# PIC18_Peripheral_breakout.net
KiCad netlist of a schematic drawn in EAGLE
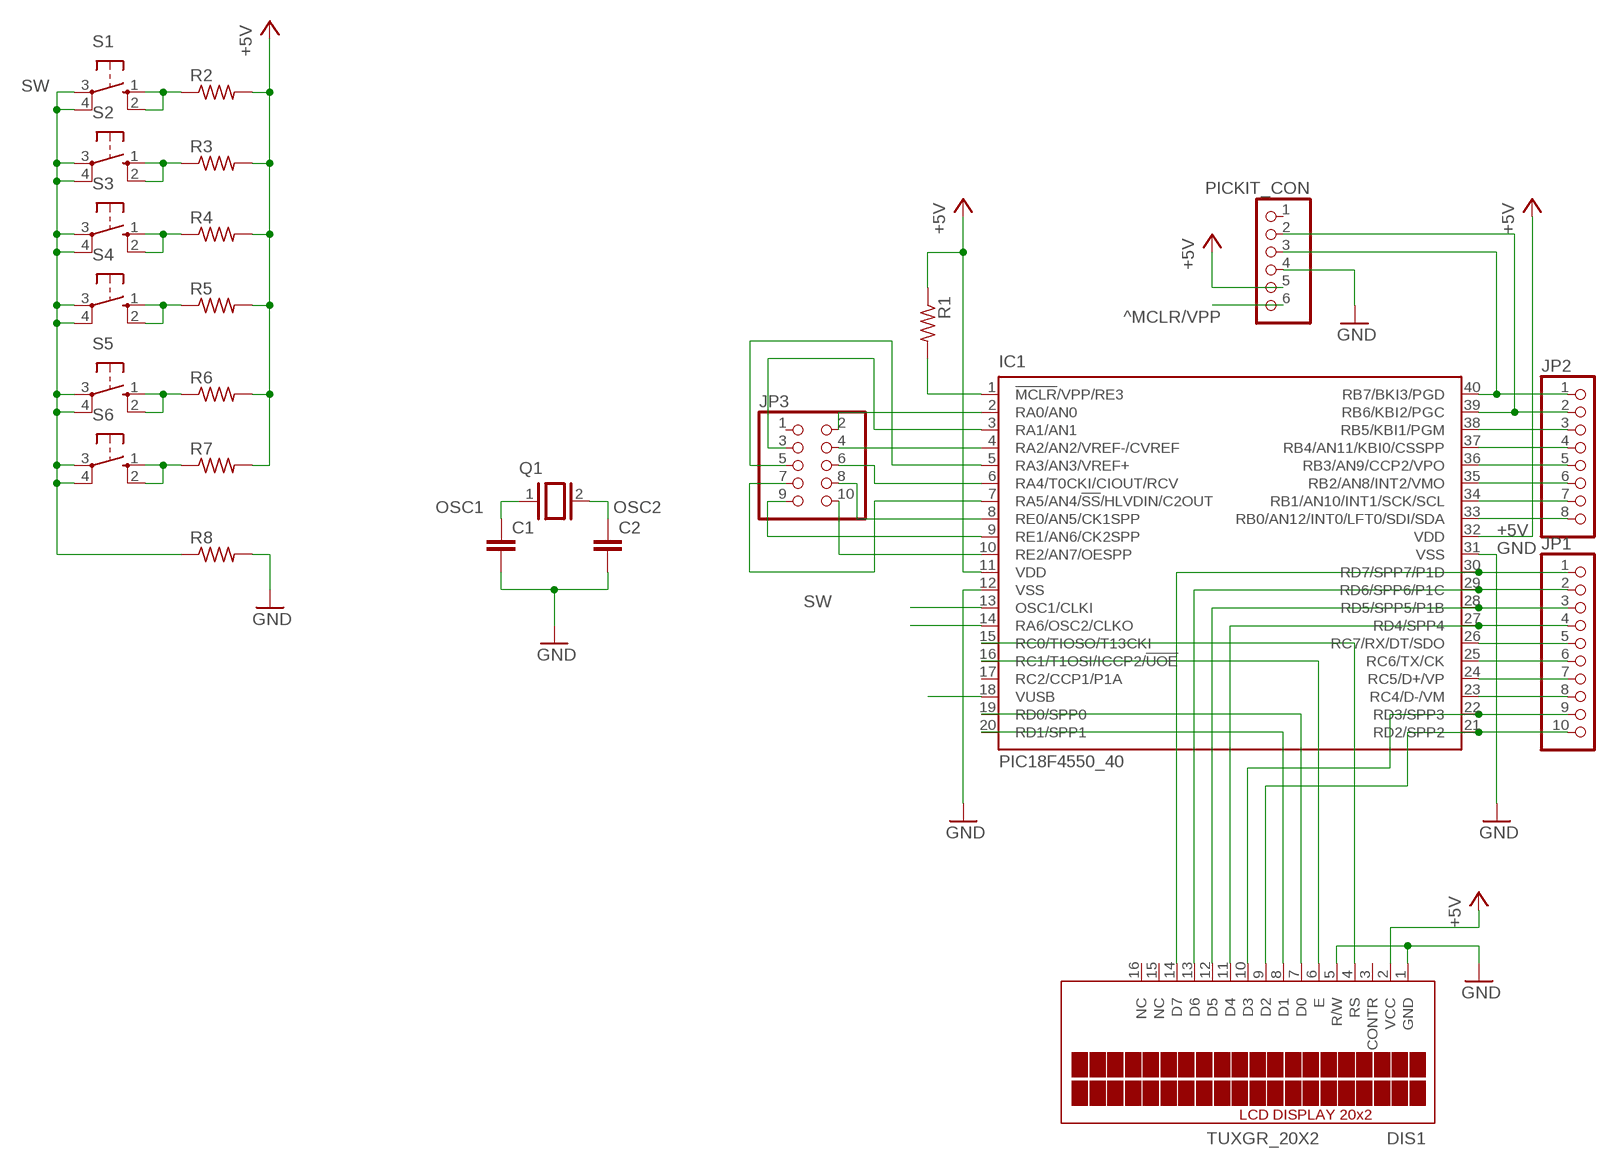
[diagram p0: schematic, sheet 1]

(export (version "E")
  (design (tool "Eeschema 10.0.6"))
  (components
    (comp (ref "C1")
      (value "C-EUC1206")
      (footprint "eagle-import:C1206")
      (libsource (lib "eagle-import") (part "C-EUC1206"))
    )
    (comp (ref "C2")
      (value "C-EUC1206")
      (footprint "eagle-import:C1206")
      (libsource (lib "eagle-import") (part "C-EUC1206"))
    )
    (comp (ref "DIS1")
      (value "TUXGR_20X2")
      (footprint "eagle-import:TUXGR_20X2")
      (libsource (lib "eagle-import") (part "TUXGR_20X2"))
    )
    (comp (ref "IC1")
      (value "PIC18F4550_40")
      (footprint "eagle-import:DIL40")
      (fields (field (name "MF") "MICROCHIP") (field (name "MPN") "PIC18F4550-I/P"))
      (libsource (lib "eagle-import") (part "PIC18F4_40550"))
    )
    (comp (ref "JP1")
      (value "PINHD-1X10")
      (footprint "eagle-import:1X10")
      (libsource (lib "eagle-import") (part "PINHD-1X10"))
    )
    (comp (ref "JP2")
      (value "PINHD-1X8")
      (footprint "eagle-import:1X08")
      (libsource (lib "eagle-import") (part "PINHD-1X8"))
    )
    (comp (ref "JP3")
      (value "PINHD-2X5")
      (footprint "eagle-import:2X05")
      (libsource (lib "eagle-import") (part "PINHD-2X5"))
    )
    (comp (ref "PICKIT_CON")
      (value "PINHD-1X6/90")
      (footprint "eagle-import:1X06_90")
      (libsource (lib "eagle-import") (part "PINHD-1X6/90"))
    )
    (comp (ref "Q1")
      (value "XTAL/S")
      (footprint "eagle-import:QS")
      (libsource (lib "eagle-import") (part "XTAL/S"))
    )
    (comp (ref "R1")
      (value "R-US_R1206")
      (footprint "eagle-import:R1206")
      (libsource (lib "eagle-import") (part "R-US_R1206"))
    )
    (comp (ref "R2")
      (value "R-US_R1206")
      (footprint "eagle-import:R1206")
      (libsource (lib "eagle-import") (part "R-US_R1206"))
    )
    (comp (ref "R3")
      (value "R-US_R1206")
      (footprint "eagle-import:R1206")
      (libsource (lib "eagle-import") (part "R-US_R1206"))
    )
    (comp (ref "R4")
      (value "R-US_R1206")
      (footprint "eagle-import:R1206")
      (libsource (lib "eagle-import") (part "R-US_R1206"))
    )
    (comp (ref "R5")
      (value "R-US_R1206")
      (footprint "eagle-import:R1206")
      (libsource (lib "eagle-import") (part "R-US_R1206"))
    )
    (comp (ref "R6")
      (value "R-US_R1206")
      (footprint "eagle-import:R1206")
      (libsource (lib "eagle-import") (part "R-US_R1206"))
    )
    (comp (ref "R7")
      (value "R-US_R1206")
      (footprint "eagle-import:R1206")
      (libsource (lib "eagle-import") (part "R-US_R1206"))
    )
    (comp (ref "R8")
      (value "R-US_R1206")
      (footprint "eagle-import:R1206")
      (libsource (lib "eagle-import") (part "R-US_R1206"))
    )
    (comp (ref "S1")
      (value "10-XX")
      (footprint "eagle-import:B3F-10XX")
      (fields (field (name "MPN") "B3F-1000"))
      (libsource (lib "eagle-import") (part "10-XX"))
    )
    (comp (ref "S2")
      (value "10-XX")
      (footprint "eagle-import:B3F-10XX")
      (fields (field (name "MPN") "B3F-1000"))
      (libsource (lib "eagle-import") (part "10-XX"))
    )
    (comp (ref "S3")
      (value "10-XX")
      (footprint "eagle-import:B3F-10XX")
      (fields (field (name "MPN") "B3F-1000"))
      (libsource (lib "eagle-import") (part "10-XX"))
    )
    (comp (ref "S4")
      (value "10-XX")
      (footprint "eagle-import:B3F-10XX")
      (fields (field (name "MPN") "B3F-1000"))
      (libsource (lib "eagle-import") (part "10-XX"))
    )
    (comp (ref "S5")
      (value "10-XX")
      (footprint "eagle-import:B3F-10XX")
      (fields (field (name "MPN") "B3F-1000"))
      (libsource (lib "eagle-import") (part "10-XX"))
    )
    (comp (ref "S6")
      (value "10-XX")
      (footprint "eagle-import:B3F-10XX")
      (fields (field (name "MPN") "B3F-1000"))
      (libsource (lib "eagle-import") (part "10-XX"))
    )
  )
  (nets
    (net (code "1") (name "+5V") (class "Default")
      (node (ref "DIS1") (pin "2") (pinfunction "VCC_2") (pintype "power_in"))
      (node (ref "IC1") (pin "11") (pinfunction "VDD_11") (pintype "power_in"))
      (node (ref "IC1") (pin "32") (pinfunction "VDD_32") (pintype "power_in"))
      (node (ref "PICKIT_CON") (pin "5") (pinfunction "5_5") (pintype "passive"))
      (node (ref "R1") (pin "1") (pinfunction "1_1") (pintype "passive"))
      (node (ref "R2") (pin "2") (pinfunction "2_2") (pintype "passive"))
      (node (ref "R3") (pin "2") (pinfunction "2_2") (pintype "passive"))
      (node (ref "R4") (pin "2") (pinfunction "2_2") (pintype "passive"))
      (node (ref "R5") (pin "2") (pinfunction "2_2") (pintype "passive"))
      (node (ref "R6") (pin "2") (pinfunction "2_2") (pintype "passive"))
      (node (ref "R7") (pin "2") (pinfunction "2_2") (pintype "passive"))
    )
    (net (code "2") (name "/OSC1") (class "Default")
      (node (ref "C1") (pin "1") (pinfunction "1_1") (pintype "passive"))
      (node (ref "IC1") (pin "13") (pinfunction "OSC1/CLKI_13") (pintype "input"))
      (node (ref "Q1") (pin "1") (pinfunction "1_1") (pintype "passive"))
    )
    (net (code "3") (name "/OSC2") (class "Default")
      (node (ref "C2") (pin "1") (pinfunction "1_1") (pintype "passive"))
      (node (ref "IC1") (pin "14") (pinfunction "RA6/OSC2/CLKO_14") (pintype "output"))
      (node (ref "Q1") (pin "2") (pinfunction "2_2") (pintype "passive"))
    )
    (net (code "4") (name "/SW") (class "Default")
      (node (ref "IC1") (pin "10") (pinfunction "RE2/AN7/OESPP_10") (pintype "bidirectional"))
      (node (ref "JP3") (pin "10") (pinfunction "10_10") (pintype "passive"))
      (node (ref "R8") (pin "1") (pinfunction "1_1") (pintype "passive"))
      (node (ref "S1") (pin "3") (pinfunction "P_3") (pintype "passive"))
      (node (ref "S1") (pin "4") (pinfunction "P1_4") (pintype "passive"))
      (node (ref "S2") (pin "3") (pinfunction "P_3") (pintype "passive"))
      (node (ref "S2") (pin "4") (pinfunction "P1_4") (pintype "passive"))
      (node (ref "S3") (pin "3") (pinfunction "P_3") (pintype "passive"))
      (node (ref "S3") (pin "4") (pinfunction "P1_4") (pintype "passive"))
      (node (ref "S4") (pin "3") (pinfunction "P_3") (pintype "passive"))
      (node (ref "S4") (pin "4") (pinfunction "P1_4") (pintype "passive"))
      (node (ref "S5") (pin "3") (pinfunction "P_3") (pintype "passive"))
      (node (ref "S5") (pin "4") (pinfunction "P1_4") (pintype "passive"))
      (node (ref "S6") (pin "3") (pinfunction "P_3") (pintype "passive"))
      (node (ref "S6") (pin "4") (pinfunction "P1_4") (pintype "passive"))
    )
    (net (code "5") (name "/^MCLR{slash}VPP") (class "Default")
      (node (ref "IC1") (pin "1") (pinfunction "~{MCLR}/VPP/RE3_1") (pintype "input"))
      (node (ref "PICKIT_CON") (pin "6") (pinfunction "6_6") (pintype "passive"))
      (node (ref "R1") (pin "2") (pinfunction "2_2") (pintype "passive"))
    )
    (net (code "6") (name "GND") (class "Default")
      (node (ref "C1") (pin "2") (pinfunction "2_2") (pintype "passive"))
      (node (ref "C2") (pin "2") (pinfunction "2_2") (pintype "passive"))
      (node (ref "DIS1") (pin "1") (pinfunction "GND_1") (pintype "power_in"))
      (node (ref "DIS1") (pin "5") (pinfunction "R/W_5") (pintype "input"))
      (node (ref "IC1") (pin "12") (pinfunction "VSS_12") (pintype "power_in"))
      (node (ref "IC1") (pin "31") (pinfunction "VSS_31") (pintype "power_in"))
      (node (ref "PICKIT_CON") (pin "4") (pinfunction "4_4") (pintype "passive"))
      (node (ref "R8") (pin "2") (pinfunction "2_2") (pintype "passive"))
    )
    (net (code "7") (name "Net-(DIS1-D0)") (class "Default")
      (node (ref "DIS1") (pin "7") (pinfunction "D0_7") (pintype "input"))
      (node (ref "IC1") (pin "19") (pinfunction "RD0/SPP0_19") (pintype "bidirectional"))
    )
    (net (code "8") (name "Net-(DIS1-D1)") (class "Default")
      (node (ref "DIS1") (pin "8") (pinfunction "D1_8") (pintype "input"))
      (node (ref "IC1") (pin "20") (pinfunction "RD1/SPP1_20") (pintype "bidirectional"))
    )
    (net (code "9") (name "Net-(DIS1-D2)") (class "Default")
      (node (ref "DIS1") (pin "9") (pinfunction "D2_9") (pintype "input"))
      (node (ref "IC1") (pin "21") (pinfunction "RD2/SPP2_21") (pintype "bidirectional"))
      (node (ref "JP1") (pin "10") (pinfunction "10_10") (pintype "passive"))
    )
    (net (code "10") (name "Net-(DIS1-D3)") (class "Default")
      (node (ref "DIS1") (pin "10") (pinfunction "D3_10") (pintype "input"))
      (node (ref "IC1") (pin "22") (pinfunction "RD3/SPP3_22") (pintype "bidirectional"))
      (node (ref "JP1") (pin "9") (pinfunction "9_9") (pintype "passive"))
    )
    (net (code "11") (name "Net-(DIS1-D4)") (class "Default")
      (node (ref "DIS1") (pin "11") (pinfunction "D4_11") (pintype "input"))
      (node (ref "IC1") (pin "27") (pinfunction "RD4/SPP4_27") (pintype "bidirectional"))
      (node (ref "JP1") (pin "4") (pinfunction "4_4") (pintype "passive"))
    )
    (net (code "12") (name "Net-(DIS1-D5)") (class "Default")
      (node (ref "DIS1") (pin "12") (pinfunction "D5_12") (pintype "input"))
      (node (ref "IC1") (pin "28") (pinfunction "RD5/SPP5/P1B_28") (pintype "bidirectional"))
      (node (ref "JP1") (pin "3") (pinfunction "3_3") (pintype "passive"))
    )
    (net (code "13") (name "Net-(DIS1-D6)") (class "Default")
      (node (ref "DIS1") (pin "13") (pinfunction "D6_13") (pintype "input"))
      (node (ref "IC1") (pin "29") (pinfunction "RD6/SPP6/P1C_29") (pintype "bidirectional"))
      (node (ref "JP1") (pin "2") (pinfunction "2_2") (pintype "passive"))
    )
    (net (code "14") (name "Net-(DIS1-D7)") (class "Default")
      (node (ref "DIS1") (pin "14") (pinfunction "D7_14") (pintype "input"))
      (node (ref "IC1") (pin "30") (pinfunction "RD7/SPP7/P1D_30") (pintype "bidirectional"))
      (node (ref "JP1") (pin "1") (pinfunction "1_1") (pintype "passive"))
    )
    (net (code "15") (name "Net-(DIS1-E)") (class "Default")
      (node (ref "DIS1") (pin "6") (pinfunction "E_6") (pintype "input"))
      (node (ref "IC1") (pin "16") (pinfunction "RC1/T1OSI/ICCP2/~{UOE}_16") (pintype "bidirectional"))
    )
    (net (code "16") (name "Net-(DIS1-RS)") (class "Default")
      (node (ref "DIS1") (pin "4") (pinfunction "RS_4") (pintype "input"))
      (node (ref "IC1") (pin "15") (pinfunction "RC0/TIOSO/T13CKI_15") (pintype "bidirectional"))
    )
    (net (code "17") (name "Net-(IC1-RA0{slash}AN0)") (class "Default")
      (node (ref "IC1") (pin "2") (pinfunction "RA0/AN0_2") (pintype "bidirectional"))
      (node (ref "JP3") (pin "2") (pinfunction "2_2") (pintype "passive"))
    )
    (net (code "18") (name "Net-(IC1-RA1{slash}AN1)") (class "Default")
      (node (ref "IC1") (pin "3") (pinfunction "RA1/AN1_3") (pintype "bidirectional"))
      (node (ref "JP3") (pin "3") (pinfunction "3_3") (pintype "passive"))
    )
    (net (code "19") (name "Net-(IC1-RA2{slash}AN2{slash}VREF-{slash}CVREF)") (class "Default")
      (node (ref "IC1") (pin "4") (pinfunction "RA2/AN2/VREF-/CVREF_4") (pintype "bidirectional"))
      (node (ref "JP3") (pin "4") (pinfunction "4_4") (pintype "passive"))
    )
    (net (code "20") (name "Net-(IC1-RA3{slash}AN3{slash}VREF+)") (class "Default")
      (node (ref "IC1") (pin "5") (pinfunction "RA3/AN3/VREF+_5") (pintype "bidirectional"))
      (node (ref "JP3") (pin "5") (pinfunction "5_5") (pintype "passive"))
    )
    (net (code "21") (name "Net-(IC1-RA4{slash}T0CKI{slash}CIOUT{slash}RCV)") (class "Default")
      (node (ref "IC1") (pin "6") (pinfunction "RA4/T0CKI/CIOUT/RCV_6") (pintype "bidirectional"))
      (node (ref "JP3") (pin "6") (pinfunction "6_6") (pintype "passive"))
    )
    (net (code "22") (name "Net-(IC1-RA5{slash}AN4{slash}~{SS}{slash}HLVDIN{slash}C2OUT)") (class "Default")
      (node (ref "IC1") (pin "7") (pinfunction "RA5/AN4/~{SS}/HLVDIN/C2OUT_7") (pintype "bidirectional"))
      (node (ref "JP3") (pin "7") (pinfunction "7_7") (pintype "passive"))
    )
    (net (code "23") (name "Net-(IC1-RB0{slash}AN12{slash}INT0{slash}LFT0{slash}SDI{slash}SDA)") (class "Default")
      (node (ref "IC1") (pin "33") (pinfunction "RB0/AN12/INT0/LFT0/SDI/SDA_33") (pintype "bidirectional"))
      (node (ref "JP2") (pin "8") (pinfunction "8_8") (pintype "passive"))
    )
    (net (code "24") (name "Net-(IC1-RB1{slash}AN10{slash}INT1{slash}SCK{slash}SCL)") (class "Default")
      (node (ref "IC1") (pin "34") (pinfunction "RB1/AN10/INT1/SCK/SCL_34") (pintype "bidirectional"))
      (node (ref "JP2") (pin "7") (pinfunction "7_7") (pintype "passive"))
    )
    (net (code "25") (name "Net-(IC1-RB2{slash}AN8{slash}INT2{slash}VMO)") (class "Default")
      (node (ref "IC1") (pin "35") (pinfunction "RB2/AN8/INT2/VMO_35") (pintype "bidirectional"))
      (node (ref "JP2") (pin "6") (pinfunction "6_6") (pintype "passive"))
    )
    (net (code "26") (name "Net-(IC1-RB3{slash}AN9{slash}CCP2{slash}VPO)") (class "Default")
      (node (ref "IC1") (pin "36") (pinfunction "RB3/AN9/CCP2/VPO_36") (pintype "bidirectional"))
      (node (ref "JP2") (pin "5") (pinfunction "5_5") (pintype "passive"))
    )
    (net (code "27") (name "Net-(IC1-RB4{slash}AN11{slash}KBI0{slash}CSSPP)") (class "Default")
      (node (ref "IC1") (pin "37") (pinfunction "RB4/AN11/KBI0/CSSPP_37") (pintype "bidirectional"))
      (node (ref "JP2") (pin "4") (pinfunction "4_4") (pintype "passive"))
    )
    (net (code "28") (name "Net-(IC1-RB5{slash}KBI1{slash}PGM)") (class "Default")
      (node (ref "IC1") (pin "38") (pinfunction "RB5/KBI1/PGM_38") (pintype "bidirectional"))
      (node (ref "JP2") (pin "3") (pinfunction "3_3") (pintype "passive"))
    )
    (net (code "29") (name "Net-(IC1-RB6{slash}KBI2{slash}PGC)") (class "Default")
      (node (ref "IC1") (pin "39") (pinfunction "RB6/KBI2/PGC_39") (pintype "bidirectional"))
      (node (ref "JP2") (pin "2") (pinfunction "2_2") (pintype "passive"))
      (node (ref "PICKIT_CON") (pin "2") (pinfunction "2_2") (pintype "passive"))
    )
    (net (code "30") (name "Net-(IC1-RB7{slash}BKI3{slash}PGD)") (class "Default")
      (node (ref "IC1") (pin "40") (pinfunction "RB7/BKI3/PGD_40") (pintype "bidirectional"))
      (node (ref "JP2") (pin "1") (pinfunction "1_1") (pintype "passive"))
      (node (ref "PICKIT_CON") (pin "3") (pinfunction "3_3") (pintype "passive"))
    )
    (net (code "31") (name "Net-(IC1-RC4{slash}D-{slash}VM)") (class "Default")
      (node (ref "IC1") (pin "23") (pinfunction "RC4/D-/VM_23") (pintype "bidirectional"))
      (node (ref "JP1") (pin "8") (pinfunction "8_8") (pintype "passive"))
    )
    (net (code "32") (name "Net-(IC1-RC5{slash}D+{slash}VP)") (class "Default")
      (node (ref "IC1") (pin "24") (pinfunction "RC5/D+/VP_24") (pintype "bidirectional"))
      (node (ref "JP1") (pin "7") (pinfunction "7_7") (pintype "passive"))
    )
    (net (code "33") (name "Net-(IC1-RC6{slash}TX{slash}CK)") (class "Default")
      (node (ref "IC1") (pin "25") (pinfunction "RC6/TX/CK_25") (pintype "bidirectional"))
      (node (ref "JP1") (pin "6") (pinfunction "6_6") (pintype "passive"))
    )
    (net (code "34") (name "Net-(IC1-RC7{slash}RX{slash}DT{slash}SDO)") (class "Default")
      (node (ref "IC1") (pin "26") (pinfunction "RC7/RX/DT/SDO_26") (pintype "bidirectional"))
      (node (ref "JP1") (pin "5") (pinfunction "5_5") (pintype "passive"))
    )
    (net (code "35") (name "Net-(IC1-RE0{slash}AN5{slash}CK1SPP)") (class "Default")
      (node (ref "IC1") (pin "8") (pinfunction "RE0/AN5/CK1SPP_8") (pintype "bidirectional"))
      (node (ref "JP3") (pin "8") (pinfunction "8_8") (pintype "passive"))
    )
    (net (code "36") (name "Net-(IC1-RE1{slash}AN6{slash}CK2SPP)") (class "Default")
      (node (ref "IC1") (pin "9") (pinfunction "RE1/AN6/CK2SPP_9") (pintype "bidirectional"))
      (node (ref "JP3") (pin "9") (pinfunction "9_9") (pintype "passive"))
    )
    (net (code "37") (name "Net-(S1-S)") (class "Default")
      (node (ref "R2") (pin "1") (pinfunction "1_1") (pintype "passive"))
      (node (ref "S1") (pin "1") (pinfunction "S_1") (pintype "passive"))
      (node (ref "S1") (pin "2") (pinfunction "S1_2") (pintype "passive"))
    )
    (net (code "38") (name "Net-(S2-S)") (class "Default")
      (node (ref "R3") (pin "1") (pinfunction "1_1") (pintype "passive"))
      (node (ref "S2") (pin "1") (pinfunction "S_1") (pintype "passive"))
      (node (ref "S2") (pin "2") (pinfunction "S1_2") (pintype "passive"))
    )
    (net (code "39") (name "Net-(S3-S)") (class "Default")
      (node (ref "R4") (pin "1") (pinfunction "1_1") (pintype "passive"))
      (node (ref "S3") (pin "1") (pinfunction "S_1") (pintype "passive"))
      (node (ref "S3") (pin "2") (pinfunction "S1_2") (pintype "passive"))
    )
    (net (code "40") (name "Net-(S4-S)") (class "Default")
      (node (ref "R5") (pin "1") (pinfunction "1_1") (pintype "passive"))
      (node (ref "S4") (pin "1") (pinfunction "S_1") (pintype "passive"))
      (node (ref "S4") (pin "2") (pinfunction "S1_2") (pintype "passive"))
    )
    (net (code "41") (name "Net-(S5-S)") (class "Default")
      (node (ref "R6") (pin "1") (pinfunction "1_1") (pintype "passive"))
      (node (ref "S5") (pin "1") (pinfunction "S_1") (pintype "passive"))
      (node (ref "S5") (pin "2") (pinfunction "S1_2") (pintype "passive"))
    )
    (net (code "42") (name "Net-(S6-S)") (class "Default")
      (node (ref "R7") (pin "1") (pinfunction "1_1") (pintype "passive"))
      (node (ref "S6") (pin "1") (pinfunction "S_1") (pintype "passive"))
      (node (ref "S6") (pin "2") (pinfunction "S1_2") (pintype "passive"))
    )
    (net (code "43") (name "unconnected-(DIS1-CONTR-Pad3)") (class "Default")
      (node (ref "DIS1") (pin "3") (pinfunction "CONTR_3") (pintype "input"))
    )
    (net (code "44") (name "unconnected-(DIS1-NC-Pad15)") (class "Default")
      (node (ref "DIS1") (pin "15") (pinfunction "NC_15") (pintype "no_connect"))
    )
    (net (code "45") (name "unconnected-(DIS1-NC-Pad16)") (class "Default")
      (node (ref "DIS1") (pin "16") (pinfunction "NC_16") (pintype "no_connect"))
    )
    (net (code "46") (name "unconnected-(IC1-RC2{slash}CCP1{slash}P1A-Pad17)") (class "Default")
      (node (ref "IC1") (pin "17") (pinfunction "RC2/CCP1/P1A_17") (pintype "bidirectional"))
    )
    (net (code "47") (name "unconnected-(IC1-VUSB-Pad18)") (class "Default")
      (node (ref "IC1") (pin "18") (pinfunction "VUSB_18") (pintype "bidirectional"))
    )
    (net (code "48") (name "unconnected-(JP3-Pad1)") (class "Default")
      (node (ref "JP3") (pin "1") (pinfunction "1_1") (pintype "passive"))
    )
    (net (code "49") (name "unconnected-(PICKIT_CON-Pad1)") (class "Default")
      (node (ref "PICKIT_CON") (pin "1") (pinfunction "1_1") (pintype "passive"))
    )
  )
)
